# Power_Circuit.net
KiCad netlist of a schematic drawn in Altium Designer
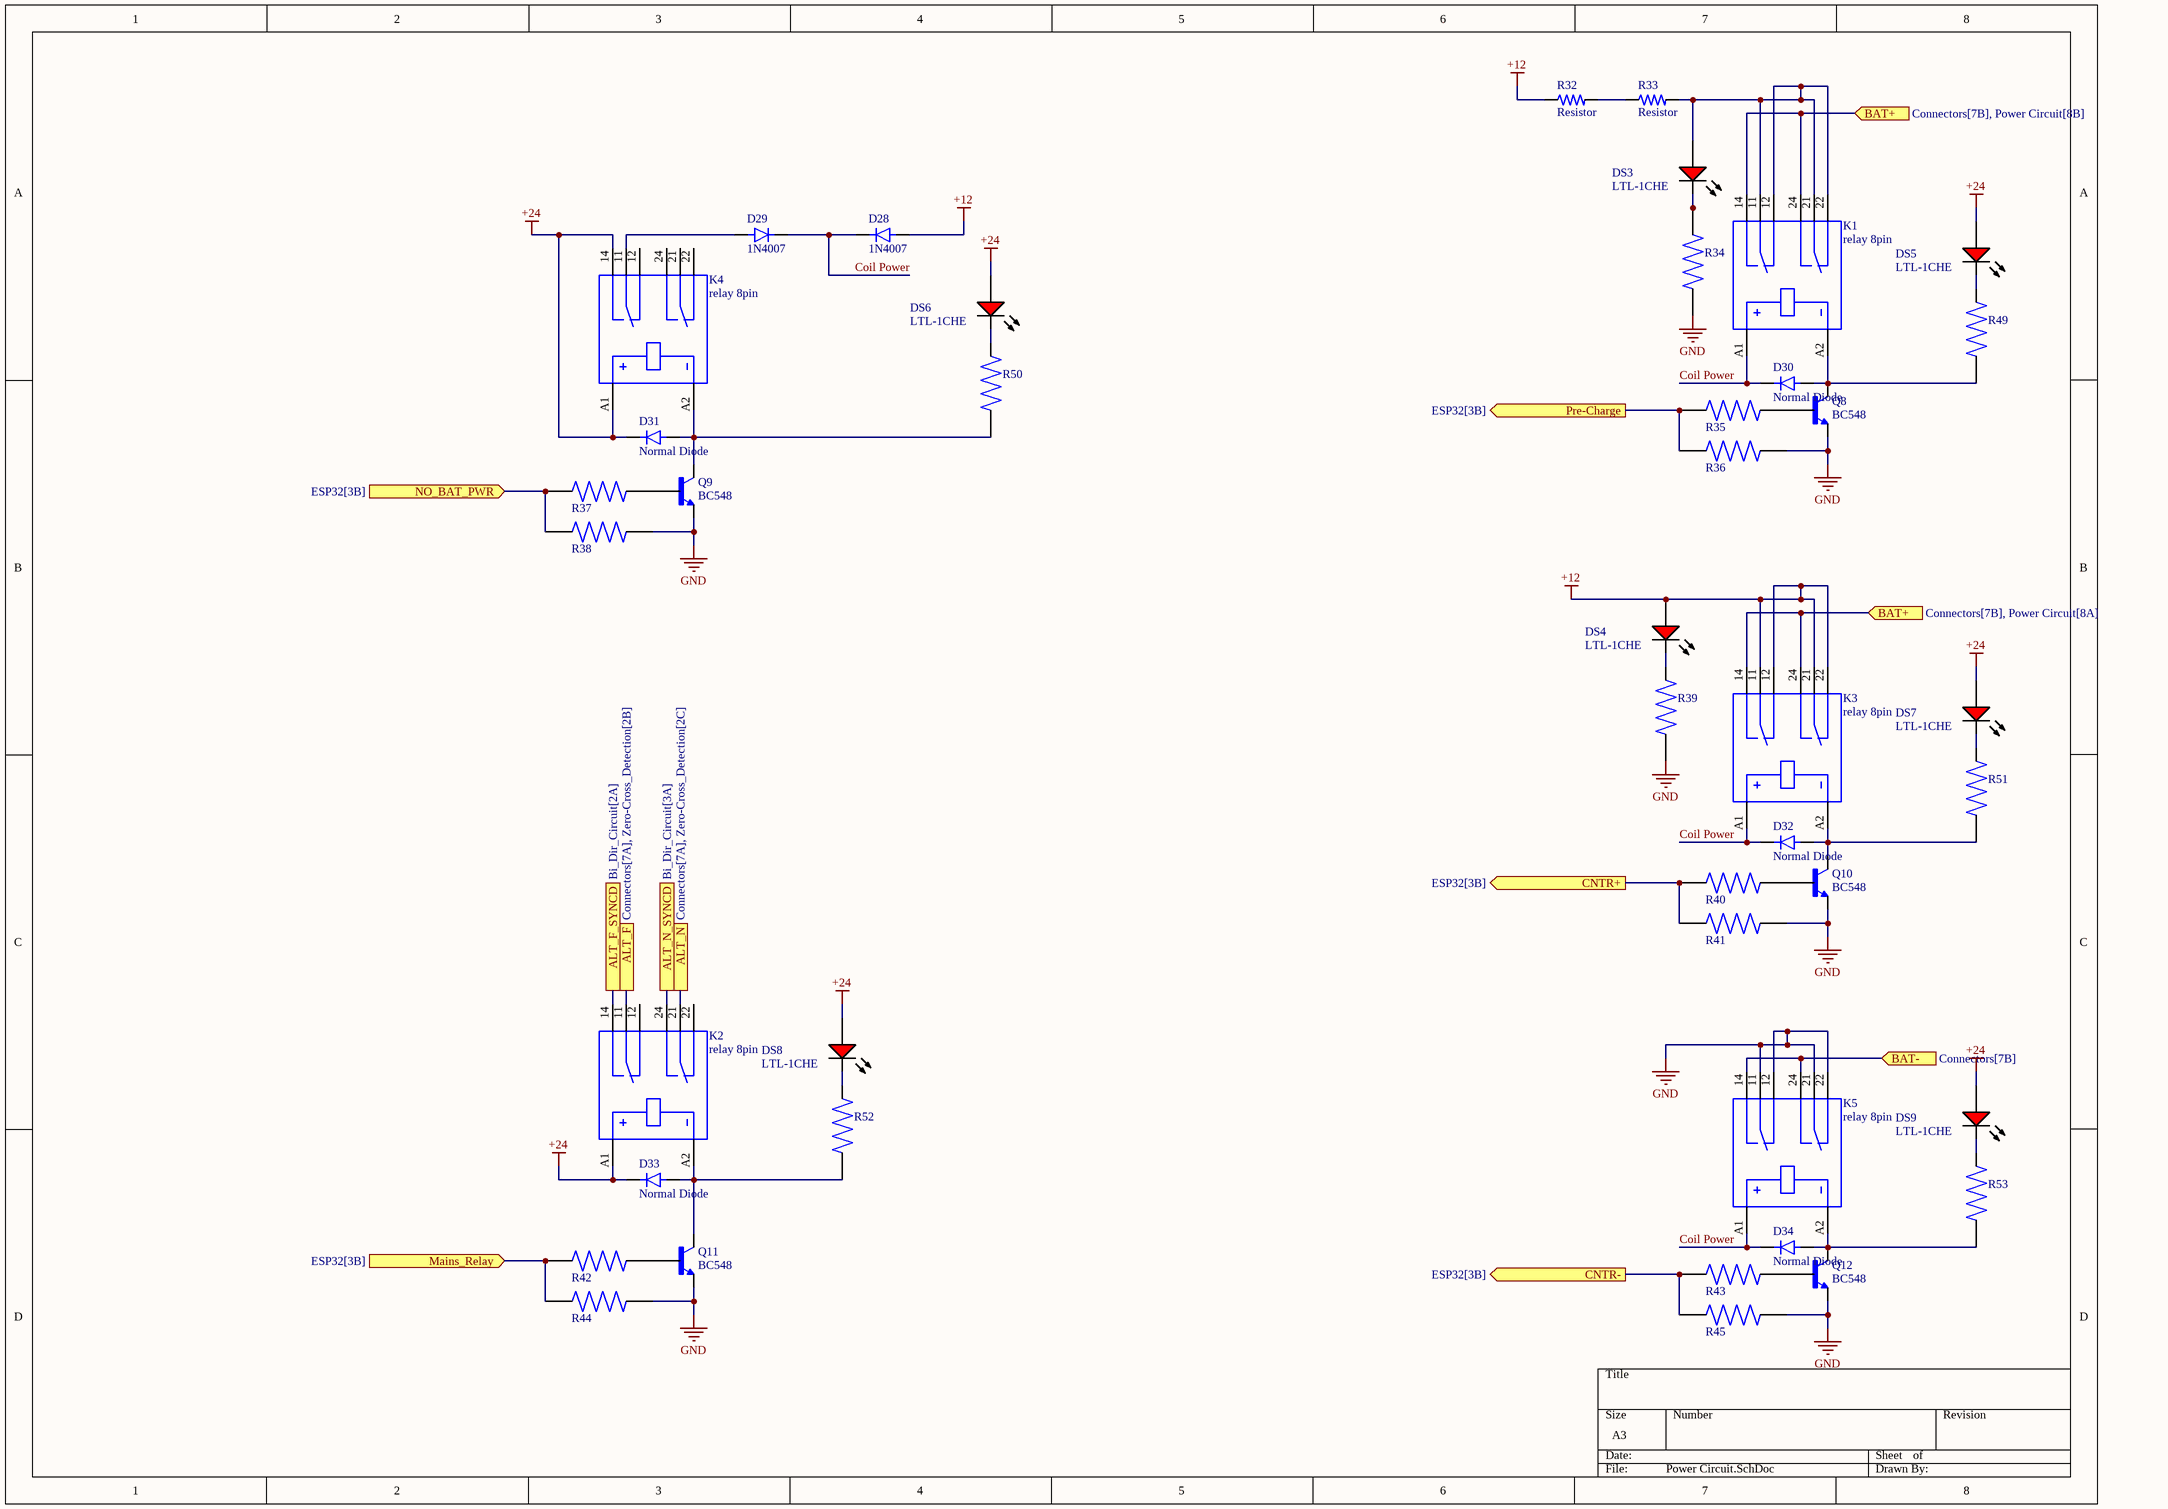
[diagram p0: Power Circuit.SchDoc]

(export (version "E")
  (design (tool "Eeschema 10.0.6"))
  (components
    (comp (ref "D28")
      (value "1N4007")
      (footprint "Common Trhough Hole")
      (fields (field (name "MF") "NTE Electronics, Inc."))
      (libsource (lib "Diodes Through Hole") (part "Normal Diode"))
    )
    (comp (ref "D29")
      (value "1N4007")
      (footprint "Common Trhough Hole")
      (fields (field (name "MF") "NTE Electronics, Inc."))
      (libsource (lib "Diodes Through Hole") (part "Normal Diode"))
    )
    (comp (ref "D30")
      (value "Normal Diode")
      (footprint "Common Trhough Hole")
      (fields (field (name "MF") "NTE Electronics, Inc.") (field (name "MP") "1N4007"))
      (libsource (lib "Diodes Through Hole") (part "Normal Diode"))
    )
    (comp (ref "D31")
      (value "Normal Diode")
      (footprint "Common Trhough Hole")
      (fields (field (name "MF") "NTE Electronics, Inc.") (field (name "MP") "1N4007"))
      (libsource (lib "Diodes Through Hole") (part "Normal Diode"))
    )
    (comp (ref "D32")
      (value "Normal Diode")
      (footprint "Common Trhough Hole")
      (fields (field (name "MF") "NTE Electronics, Inc.") (field (name "MP") "1N4007"))
      (libsource (lib "Diodes Through Hole") (part "Normal Diode"))
    )
    (comp (ref "D33")
      (value "Normal Diode")
      (footprint "Common Trhough Hole")
      (fields (field (name "MF") "NTE Electronics, Inc.") (field (name "MP") "1N4007"))
      (libsource (lib "Diodes Through Hole") (part "Normal Diode"))
    )
    (comp (ref "D34")
      (value "Normal Diode")
      (footprint "Common Trhough Hole")
      (fields (field (name "MF") "NTE Electronics, Inc.") (field (name "MP") "1N4007"))
      (libsource (lib "Diodes Through Hole") (part "Normal Diode"))
    )
    (comp (ref "DS3")
      (value "LTL-1CHE")
      (footprint "LED3mm")
      (description "Radial LED, 12.6 mcd, 20 mA, 2 V, -55 to 100 degC, 2-Pin THD, RoHS, Bulk")
      (fields (field (name "TOLERANCE") "20%"))
      (libsource (lib "MySCH_Library") (part "RED_LED 3mm"))
    )
    (comp (ref "DS4")
      (value "LTL-1CHE")
      (footprint "LED3mm")
      (description "Radial LED, 12.6 mcd, 20 mA, 2 V, -55 to 100 degC, 2-Pin THD, RoHS, Bulk")
      (fields (field (name "TOLERANCE") "20%"))
      (libsource (lib "MySCH_Library") (part "RED_LED 3mm"))
    )
    (comp (ref "DS5")
      (value "LTL-1CHE")
      (footprint "LED3mm")
      (description "Radial LED, 12.6 mcd, 20 mA, 2 V, -55 to 100 degC, 2-Pin THD, RoHS, Bulk")
      (fields (field (name "TOLERANCE") "20%"))
      (libsource (lib "MySCH_Library") (part "RED_LED 3mm"))
    )
    (comp (ref "DS6")
      (value "LTL-1CHE")
      (footprint "LED3mm")
      (description "Radial LED, 12.6 mcd, 20 mA, 2 V, -55 to 100 degC, 2-Pin THD, RoHS, Bulk")
      (fields (field (name "TOLERANCE") "20%"))
      (libsource (lib "MySCH_Library") (part "RED_LED 3mm"))
    )
    (comp (ref "DS7")
      (value "LTL-1CHE")
      (footprint "LED3mm")
      (description "Radial LED, 12.6 mcd, 20 mA, 2 V, -55 to 100 degC, 2-Pin THD, RoHS, Bulk")
      (fields (field (name "TOLERANCE") "20%"))
      (libsource (lib "MySCH_Library") (part "RED_LED 3mm"))
    )
    (comp (ref "DS8")
      (value "LTL-1CHE")
      (footprint "LED3mm")
      (description "Radial LED, 12.6 mcd, 20 mA, 2 V, -55 to 100 degC, 2-Pin THD, RoHS, Bulk")
      (fields (field (name "TOLERANCE") "20%"))
      (libsource (lib "MySCH_Library") (part "RED_LED 3mm"))
    )
    (comp (ref "DS9")
      (value "LTL-1CHE")
      (footprint "LED3mm")
      (description "Radial LED, 12.6 mcd, 20 mA, 2 V, -55 to 100 degC, 2-Pin THD, RoHS, Bulk")
      (fields (field (name "TOLERANCE") "20%"))
      (libsource (lib "MySCH_Library") (part "RED_LED 3mm"))
    )
    (comp (ref "K1")
      (value "relay 8pin")
      (footprint "Relay socket 8pin")
      (description "General Purpose Relay DPDT _2 Form C_ 24VDC Coil Through Hole")
      (fields (field (name "MF") "TE Connectivity") (field (name "MP") "1-1393243-0"))
      (libsource (lib "MySCH_Library") (part "relay 8pin"))
    )
    (comp (ref "K2")
      (value "relay 8pin")
      (footprint "Relay socket 8pin")
      (description "General Purpose Relay DPDT _2 Form C_ 24VDC Coil Through Hole")
      (fields (field (name "MF") "TE Connectivity") (field (name "MP") "1-1393243-0"))
      (libsource (lib "MySCH_Library") (part "relay 8pin"))
    )
    (comp (ref "K3")
      (value "relay 8pin")
      (footprint "Relay socket 8pin")
      (description "General Purpose Relay DPDT _2 Form C_ 24VDC Coil Through Hole")
      (fields (field (name "MF") "TE Connectivity") (field (name "MP") "1-1393243-0"))
      (libsource (lib "MySCH_Library") (part "relay 8pin"))
    )
    (comp (ref "K4")
      (value "relay 8pin")
      (footprint "Relay socket 8pin")
      (description "General Purpose Relay DPDT _2 Form C_ 24VDC Coil Through Hole")
      (fields (field (name "MF") "TE Connectivity") (field (name "MP") "1-1393243-0"))
      (libsource (lib "MySCH_Library") (part "relay 8pin"))
    )
    (comp (ref "K5")
      (value "relay 8pin")
      (footprint "Relay socket 8pin")
      (description "General Purpose Relay DPDT _2 Form C_ 24VDC Coil Through Hole")
      (fields (field (name "MF") "TE Connectivity") (field (name "MP") "1-1393243-0"))
      (libsource (lib "MySCH_Library") (part "relay 8pin"))
    )
    (comp (ref "Q8")
      (value "BC548")
      (footprint "bc548")
      (description "Bipolar (BJT) Transistor NPN 30V 100mA 300MHz 500mW Through Hole TO-92-3")
      (fields (field (name "MF") "ON Semiconductor"))
      (libsource (lib "MySCH_Library") (part "BC548"))
    )
    (comp (ref "Q9")
      (value "BC548")
      (footprint "bc548")
      (description "Bipolar (BJT) Transistor NPN 30V 100mA 300MHz 500mW Through Hole TO-92-3")
      (fields (field (name "MF") "ON Semiconductor"))
      (libsource (lib "MySCH_Library") (part "BC548"))
    )
    (comp (ref "Q10")
      (value "BC548")
      (footprint "bc548")
      (description "Bipolar (BJT) Transistor NPN 30V 100mA 300MHz 500mW Through Hole TO-92-3")
      (fields (field (name "MF") "ON Semiconductor"))
      (libsource (lib "MySCH_Library") (part "BC548"))
    )
    (comp (ref "Q11")
      (value "BC548")
      (footprint "bc548")
      (description "Bipolar (BJT) Transistor NPN 30V 100mA 300MHz 500mW Through Hole TO-92-3")
      (fields (field (name "MF") "ON Semiconductor"))
      (libsource (lib "MySCH_Library") (part "BC548"))
    )
    (comp (ref "Q12")
      (value "BC548")
      (footprint "bc548")
      (description "Bipolar (BJT) Transistor NPN 30V 100mA 300MHz 500mW Through Hole TO-92-3")
      (fields (field (name "MF") "ON Semiconductor"))
      (libsource (lib "MySCH_Library") (part "BC548"))
    )
    (comp (ref "R32")
      (value "Resistor")
      (footprint "Resistor_Through Hole")
      (fields
        (field (name "MP") "2-2176053-0")
        (field (name "TOLERANCE") "1%")
        (field (name "MF") "TE Connectivity")
      )
      (libsource (lib "Resistors Through Hole") (part "Resistor"))
    )
    (comp (ref "R33")
      (value "Resistor")
      (footprint "Resistor_Through Hole")
      (fields
        (field (name "MP") "2-2176053-0")
        (field (name "TOLERANCE") "1%")
        (field (name "MF") "TE Connectivity")
      )
      (libsource (lib "Resistors Through Hole") (part "Resistor"))
    )
    (comp (ref "R34")
      (value "Resistor_Through Hole")
      (footprint "Resistor_Through Hole")
      (description "1.02 Ohms Â±1% 0.25W, 1/4W Through Hole Resistor Axial Metal Film")
      (fields (field (name "MP") "MFR-25FTE52-1R") (field (name "MF") "Yageo"))
      (libsource (lib "MySCH_Library") (part "Resistor_Through Hole"))
    )
    (comp (ref "R35")
      (value "Resistor_Through Hole")
      (footprint "Resistor_Through Hole")
      (description "1.02 Ohms Â±1% 0.25W, 1/4W Through Hole Resistor Axial Metal Film")
      (fields (field (name "MP") "MFR-25FTE52-1R") (field (name "MF") "Yageo"))
      (libsource (lib "MySCH_Library") (part "Resistor_Through Hole"))
    )
    (comp (ref "R36")
      (value "Resistor_Through Hole")
      (footprint "Resistor_Through Hole")
      (description "1.02 Ohms Â±1% 0.25W, 1/4W Through Hole Resistor Axial Metal Film")
      (fields (field (name "MP") "MFR-25FTE52-1R") (field (name "MF") "Yageo"))
      (libsource (lib "MySCH_Library") (part "Resistor_Through Hole"))
    )
    (comp (ref "R37")
      (value "Resistor_Through Hole")
      (footprint "Resistor_Through Hole")
      (description "1.02 Ohms Â±1% 0.25W, 1/4W Through Hole Resistor Axial Metal Film")
      (fields (field (name "MP") "MFR-25FTE52-1R") (field (name "MF") "Yageo"))
      (libsource (lib "MySCH_Library") (part "Resistor_Through Hole"))
    )
    (comp (ref "R38")
      (value "Resistor_Through Hole")
      (footprint "Resistor_Through Hole")
      (description "1.02 Ohms Â±1% 0.25W, 1/4W Through Hole Resistor Axial Metal Film")
      (fields (field (name "MP") "MFR-25FTE52-1R") (field (name "MF") "Yageo"))
      (libsource (lib "MySCH_Library") (part "Resistor_Through Hole"))
    )
    (comp (ref "R39")
      (value "Resistor_Through Hole")
      (footprint "Resistor_Through Hole")
      (description "1.02 Ohms Â±1% 0.25W, 1/4W Through Hole Resistor Axial Metal Film")
      (fields (field (name "MP") "MFR-25FTE52-1R") (field (name "MF") "Yageo"))
      (libsource (lib "MySCH_Library") (part "Resistor_Through Hole"))
    )
    (comp (ref "R40")
      (value "Resistor_Through Hole")
      (footprint "Resistor_Through Hole")
      (description "1.02 Ohms Â±1% 0.25W, 1/4W Through Hole Resistor Axial Metal Film")
      (fields (field (name "MP") "MFR-25FTE52-1R") (field (name "MF") "Yageo"))
      (libsource (lib "MySCH_Library") (part "Resistor_Through Hole"))
    )
    (comp (ref "R41")
      (value "Resistor_Through Hole")
      (footprint "Resistor_Through Hole")
      (description "1.02 Ohms Â±1% 0.25W, 1/4W Through Hole Resistor Axial Metal Film")
      (fields (field (name "MP") "MFR-25FTE52-1R") (field (name "MF") "Yageo"))
      (libsource (lib "MySCH_Library") (part "Resistor_Through Hole"))
    )
    (comp (ref "R42")
      (value "Resistor_Through Hole")
      (footprint "Resistor_Through Hole")
      (description "1.02 Ohms Â±1% 0.25W, 1/4W Through Hole Resistor Axial Metal Film")
      (fields (field (name "MP") "MFR-25FTE52-1R") (field (name "MF") "Yageo"))
      (libsource (lib "MySCH_Library") (part "Resistor_Through Hole"))
    )
    (comp (ref "R43")
      (value "Resistor_Through Hole")
      (footprint "Resistor_Through Hole")
      (description "1.02 Ohms Â±1% 0.25W, 1/4W Through Hole Resistor Axial Metal Film")
      (fields (field (name "MP") "MFR-25FTE52-1R") (field (name "MF") "Yageo"))
      (libsource (lib "MySCH_Library") (part "Resistor_Through Hole"))
    )
    (comp (ref "R44")
      (value "Resistor_Through Hole")
      (footprint "Resistor_Through Hole")
      (description "1.02 Ohms Â±1% 0.25W, 1/4W Through Hole Resistor Axial Metal Film")
      (fields (field (name "MP") "MFR-25FTE52-1R") (field (name "MF") "Yageo"))
      (libsource (lib "MySCH_Library") (part "Resistor_Through Hole"))
    )
    (comp (ref "R45")
      (value "Resistor_Through Hole")
      (footprint "Resistor_Through Hole")
      (description "1.02 Ohms Â±1% 0.25W, 1/4W Through Hole Resistor Axial Metal Film")
      (fields (field (name "MP") "MFR-25FTE52-1R") (field (name "MF") "Yageo"))
      (libsource (lib "MySCH_Library") (part "Resistor_Through Hole"))
    )
    (comp (ref "R49")
      (value "Resistor_Through Hole")
      (footprint "Resistor_Through Hole")
      (description "1.02 Ohms Â±1% 0.25W, 1/4W Through Hole Resistor Axial Metal Film")
      (fields (field (name "MP") "MFR-25FTE52-1R") (field (name "MF") "Yageo"))
      (libsource (lib "MySCH_Library") (part "Resistor_Through Hole"))
    )
    (comp (ref "R50")
      (value "Resistor_Through Hole")
      (footprint "Resistor_Through Hole")
      (description "1.02 Ohms Â±1% 0.25W, 1/4W Through Hole Resistor Axial Metal Film")
      (fields (field (name "MP") "MFR-25FTE52-1R") (field (name "MF") "Yageo"))
      (libsource (lib "MySCH_Library") (part "Resistor_Through Hole"))
    )
    (comp (ref "R51")
      (value "Resistor_Through Hole")
      (footprint "Resistor_Through Hole")
      (description "1.02 Ohms Â±1% 0.25W, 1/4W Through Hole Resistor Axial Metal Film")
      (fields (field (name "MP") "MFR-25FTE52-1R") (field (name "MF") "Yageo"))
      (libsource (lib "MySCH_Library") (part "Resistor_Through Hole"))
    )
    (comp (ref "R52")
      (value "Resistor_Through Hole")
      (footprint "Resistor_Through Hole")
      (description "1.02 Ohms Â±1% 0.25W, 1/4W Through Hole Resistor Axial Metal Film")
      (fields (field (name "MP") "MFR-25FTE52-1R") (field (name "MF") "Yageo"))
      (libsource (lib "MySCH_Library") (part "Resistor_Through Hole"))
    )
    (comp (ref "R53")
      (value "Resistor_Through Hole")
      (footprint "Resistor_Through Hole")
      (description "1.02 Ohms Â±1% 0.25W, 1/4W Through Hole Resistor Axial Metal Film")
      (fields (field (name "MP") "MFR-25FTE52-1R") (field (name "MF") "Yageo"))
      (libsource (lib "MySCH_Library") (part "Resistor_Through Hole"))
    )
  )
  (nets
    (net (code "1") (name "+12") (class "Default")
      (node (ref "D28") (pin "2") (pinfunction "A_2") (pintype "passive"))
      (node (ref "DS4") (pin "1") (pinfunction "A_1") (pintype "passive"))
      (node (ref "K3") (pin "11") (pinfunction "6_11") (pintype "passive"))
      (node (ref "K3") (pin "12") (pinfunction "7_12") (pintype "passive"))
      (node (ref "K3") (pin "21") (pinfunction "3_21") (pintype "passive"))
      (node (ref "K3") (pin "22") (pinfunction "2_22") (pintype "passive"))
      (node (ref "R32") (pin "1") (pinfunction "1_1") (pintype "passive"))
    )
    (net (code "2") (name "+24") (class "Default")
      (node (ref "D31") (pin "1") (pinfunction "K_1") (pintype "passive"))
      (node (ref "D33") (pin "1") (pinfunction "K_1") (pintype "passive"))
      (node (ref "DS5") (pin "1") (pinfunction "A_1") (pintype "passive"))
      (node (ref "DS6") (pin "1") (pinfunction "A_1") (pintype "passive"))
      (node (ref "DS7") (pin "1") (pinfunction "A_1") (pintype "passive"))
      (node (ref "DS8") (pin "1") (pinfunction "A_1") (pintype "passive"))
      (node (ref "DS9") (pin "1") (pinfunction "A_1") (pintype "passive"))
      (node (ref "K2") (pin "A1") (pinfunction "1_A1") (pintype "passive"))
      (node (ref "K4") (pin "14") (pinfunction "5_14") (pintype "passive"))
      (node (ref "K4") (pin "A1") (pinfunction "1_A1") (pintype "passive"))
    )
    (net (code "3") (name "/ALT_F") (class "Default")
      (node (ref "K2") (pin "11") (pinfunction "6_11") (pintype "passive"))
    )
    (net (code "4") (name "/ALT_F_SYNCD") (class "Default")
      (node (ref "K2") (pin "14") (pinfunction "5_14") (pintype "passive"))
    )
    (net (code "5") (name "/ALT_N") (class "Default")
      (node (ref "K2") (pin "21") (pinfunction "3_21") (pintype "passive"))
    )
    (net (code "6") (name "/ALT_N_SYNCD") (class "Default")
      (node (ref "K2") (pin "24") (pinfunction "4_24") (pintype "passive"))
    )
    (net (code "7") (name "/BAT+") (class "Default")
      (node (ref "K1") (pin "14") (pinfunction "5_14") (pintype "passive"))
      (node (ref "K1") (pin "24") (pinfunction "4_24") (pintype "passive"))
      (node (ref "K3") (pin "14") (pinfunction "5_14") (pintype "passive"))
      (node (ref "K3") (pin "24") (pinfunction "4_24") (pintype "passive"))
    )
    (net (code "8") (name "/BAT-") (class "Default")
      (node (ref "K5") (pin "14") (pinfunction "5_14") (pintype "passive"))
      (node (ref "K5") (pin "24") (pinfunction "4_24") (pintype "passive"))
    )
    (net (code "9") (name "/CNTR+") (class "Default")
      (node (ref "R40") (pin "2") (pinfunction "2_2") (pintype "passive"))
      (node (ref "R41") (pin "2") (pinfunction "2_2") (pintype "passive"))
    )
    (net (code "10") (name "/CNTR-") (class "Default")
      (node (ref "R43") (pin "2") (pinfunction "2_2") (pintype "passive"))
      (node (ref "R45") (pin "2") (pinfunction "2_2") (pintype "passive"))
    )
    (net (code "11") (name "/Coil Power") (class "Default")
      (node (ref "D28") (pin "1") (pinfunction "K_1") (pintype "passive"))
      (node (ref "D29") (pin "1") (pinfunction "K_1") (pintype "passive"))
      (node (ref "D30") (pin "1") (pinfunction "K_1") (pintype "passive"))
      (node (ref "D32") (pin "1") (pinfunction "K_1") (pintype "passive"))
      (node (ref "D34") (pin "1") (pinfunction "K_1") (pintype "passive"))
      (node (ref "K1") (pin "A1") (pinfunction "1_A1") (pintype "passive"))
      (node (ref "K3") (pin "A1") (pinfunction "1_A1") (pintype "passive"))
      (node (ref "K5") (pin "A1") (pinfunction "1_A1") (pintype "passive"))
    )
    (net (code "12") (name "/Mains_Relay") (class "Default")
      (node (ref "R42") (pin "2") (pinfunction "2_2") (pintype "passive"))
      (node (ref "R44") (pin "2") (pinfunction "2_2") (pintype "passive"))
    )
    (net (code "13") (name "/NO_BAT_PWR") (class "Default")
      (node (ref "R37") (pin "2") (pinfunction "2_2") (pintype "passive"))
      (node (ref "R38") (pin "2") (pinfunction "2_2") (pintype "passive"))
    )
    (net (code "14") (name "/Pre-Charge") (class "Default")
      (node (ref "R35") (pin "2") (pinfunction "2_2") (pintype "passive"))
      (node (ref "R36") (pin "2") (pinfunction "2_2") (pintype "passive"))
    )
    (net (code "15") (name "GND") (class "Default")
      (node (ref "K5") (pin "11") (pinfunction "6_11") (pintype "passive"))
      (node (ref "K5") (pin "12") (pinfunction "7_12") (pintype "passive"))
      (node (ref "K5") (pin "21") (pinfunction "3_21") (pintype "passive"))
      (node (ref "K5") (pin "22") (pinfunction "2_22") (pintype "passive"))
      (node (ref "Q10") (pin "3") (pinfunction "E_3") (pintype "passive"))
      (node (ref "Q11") (pin "3") (pinfunction "E_3") (pintype "passive"))
      (node (ref "Q12") (pin "3") (pinfunction "E_3") (pintype "passive"))
      (node (ref "Q8") (pin "3") (pinfunction "E_3") (pintype "passive"))
      (node (ref "Q9") (pin "3") (pinfunction "E_3") (pintype "passive"))
      (node (ref "R34") (pin "2") (pinfunction "2_2") (pintype "passive"))
      (node (ref "R36") (pin "1") (pinfunction "1_1") (pintype "passive"))
      (node (ref "R38") (pin "1") (pinfunction "1_1") (pintype "passive"))
      (node (ref "R39") (pin "2") (pinfunction "2_2") (pintype "passive"))
      (node (ref "R41") (pin "1") (pinfunction "1_1") (pintype "passive"))
      (node (ref "R44") (pin "1") (pinfunction "1_1") (pintype "passive"))
      (node (ref "R45") (pin "1") (pinfunction "1_1") (pintype "passive"))
    )
    (net (code "16") (name "Net-(D29-A)") (class "Default")
      (node (ref "D29") (pin "2") (pinfunction "A_2") (pintype "passive"))
      (node (ref "K4") (pin "11") (pinfunction "6_11") (pintype "passive"))
    )
    (net (code "17") (name "Net-(D30-A)") (class "Default")
      (node (ref "D30") (pin "2") (pinfunction "A_2") (pintype "passive"))
      (node (ref "K1") (pin "A2") (pinfunction "8_A2") (pintype "passive"))
      (node (ref "Q8") (pin "1") (pinfunction "C_1") (pintype "passive"))
      (node (ref "R49") (pin "2") (pinfunction "2_2") (pintype "passive"))
    )
    (net (code "18") (name "Net-(D31-A)") (class "Default")
      (node (ref "D31") (pin "2") (pinfunction "A_2") (pintype "passive"))
      (node (ref "K4") (pin "A2") (pinfunction "8_A2") (pintype "passive"))
      (node (ref "Q9") (pin "1") (pinfunction "C_1") (pintype "passive"))
      (node (ref "R50") (pin "2") (pinfunction "2_2") (pintype "passive"))
    )
    (net (code "19") (name "Net-(D32-A)") (class "Default")
      (node (ref "D32") (pin "2") (pinfunction "A_2") (pintype "passive"))
      (node (ref "K3") (pin "A2") (pinfunction "8_A2") (pintype "passive"))
      (node (ref "Q10") (pin "1") (pinfunction "C_1") (pintype "passive"))
      (node (ref "R51") (pin "2") (pinfunction "2_2") (pintype "passive"))
    )
    (net (code "20") (name "Net-(D33-A)") (class "Default")
      (node (ref "D33") (pin "2") (pinfunction "A_2") (pintype "passive"))
      (node (ref "K2") (pin "A2") (pinfunction "8_A2") (pintype "passive"))
      (node (ref "Q11") (pin "1") (pinfunction "C_1") (pintype "passive"))
      (node (ref "R52") (pin "2") (pinfunction "2_2") (pintype "passive"))
    )
    (net (code "21") (name "Net-(D34-A)") (class "Default")
      (node (ref "D34") (pin "2") (pinfunction "A_2") (pintype "passive"))
      (node (ref "K5") (pin "A2") (pinfunction "8_A2") (pintype "passive"))
      (node (ref "Q12") (pin "1") (pinfunction "C_1") (pintype "passive"))
      (node (ref "R53") (pin "2") (pinfunction "2_2") (pintype "passive"))
    )
    (net (code "22") (name "Net-(DS3-A)") (class "Default")
      (node (ref "DS3") (pin "1") (pinfunction "A_1") (pintype "passive"))
      (node (ref "K1") (pin "11") (pinfunction "6_11") (pintype "passive"))
      (node (ref "K1") (pin "12") (pinfunction "7_12") (pintype "passive"))
      (node (ref "K1") (pin "21") (pinfunction "3_21") (pintype "passive"))
      (node (ref "K1") (pin "22") (pinfunction "2_22") (pintype "passive"))
      (node (ref "R33") (pin "2") (pinfunction "2_2") (pintype "passive"))
    )
    (net (code "23") (name "Net-(DS3-K)") (class "Default")
      (node (ref "DS3") (pin "2") (pinfunction "K_2") (pintype "passive"))
      (node (ref "R34") (pin "1") (pinfunction "1_1") (pintype "passive"))
    )
    (net (code "24") (name "Net-(DS4-K)") (class "Default")
      (node (ref "DS4") (pin "2") (pinfunction "K_2") (pintype "passive"))
      (node (ref "R39") (pin "1") (pinfunction "1_1") (pintype "passive"))
    )
    (net (code "25") (name "Net-(DS5-K)") (class "Default")
      (node (ref "DS5") (pin "2") (pinfunction "K_2") (pintype "passive"))
      (node (ref "R49") (pin "1") (pinfunction "1_1") (pintype "passive"))
    )
    (net (code "26") (name "Net-(DS6-K)") (class "Default")
      (node (ref "DS6") (pin "2") (pinfunction "K_2") (pintype "passive"))
      (node (ref "R50") (pin "1") (pinfunction "1_1") (pintype "passive"))
    )
    (net (code "27") (name "Net-(DS7-K)") (class "Default")
      (node (ref "DS7") (pin "2") (pinfunction "K_2") (pintype "passive"))
      (node (ref "R51") (pin "1") (pinfunction "1_1") (pintype "passive"))
    )
    (net (code "28") (name "Net-(DS8-K)") (class "Default")
      (node (ref "DS8") (pin "2") (pinfunction "K_2") (pintype "passive"))
      (node (ref "R52") (pin "1") (pinfunction "1_1") (pintype "passive"))
    )
    (net (code "29") (name "Net-(DS9-K)") (class "Default")
      (node (ref "DS9") (pin "2") (pinfunction "K_2") (pintype "passive"))
      (node (ref "R53") (pin "1") (pinfunction "1_1") (pintype "passive"))
    )
    (net (code "30") (name "Net-(Q8-B)") (class "Default")
      (node (ref "Q8") (pin "2") (pinfunction "B_2") (pintype "passive"))
      (node (ref "R35") (pin "1") (pinfunction "1_1") (pintype "passive"))
    )
    (net (code "31") (name "Net-(Q9-B)") (class "Default")
      (node (ref "Q9") (pin "2") (pinfunction "B_2") (pintype "passive"))
      (node (ref "R37") (pin "1") (pinfunction "1_1") (pintype "passive"))
    )
    (net (code "32") (name "Net-(Q10-B)") (class "Default")
      (node (ref "Q10") (pin "2") (pinfunction "B_2") (pintype "passive"))
      (node (ref "R40") (pin "1") (pinfunction "1_1") (pintype "passive"))
    )
    (net (code "33") (name "Net-(Q11-B)") (class "Default")
      (node (ref "Q11") (pin "2") (pinfunction "B_2") (pintype "passive"))
      (node (ref "R42") (pin "1") (pinfunction "1_1") (pintype "passive"))
    )
    (net (code "34") (name "Net-(Q12-B)") (class "Default")
      (node (ref "Q12") (pin "2") (pinfunction "B_2") (pintype "passive"))
      (node (ref "R43") (pin "1") (pinfunction "1_1") (pintype "passive"))
    )
    (net (code "35") (name "Net-(R32-Pad2)") (class "Default")
      (node (ref "R32") (pin "2") (pinfunction "2_2") (pintype "passive"))
      (node (ref "R33") (pin "1") (pinfunction "1_1") (pintype "passive"))
    )
    (net (code "36") (name "unconnected-(K2-2-Pad22)") (class "Default")
      (node (ref "K2") (pin "22") (pinfunction "2_22") (pintype "passive"))
    )
    (net (code "37") (name "unconnected-(K2-7-Pad12)") (class "Default")
      (node (ref "K2") (pin "12") (pinfunction "7_12") (pintype "passive"))
    )
    (net (code "38") (name "unconnected-(K4-2-Pad22)") (class "Default")
      (node (ref "K4") (pin "22") (pinfunction "2_22") (pintype "passive"))
    )
    (net (code "39") (name "unconnected-(K4-3-Pad21)") (class "Default")
      (node (ref "K4") (pin "21") (pinfunction "3_21") (pintype "passive"))
    )
    (net (code "40") (name "unconnected-(K4-4-Pad24)") (class "Default")
      (node (ref "K4") (pin "24") (pinfunction "4_24") (pintype "passive"))
    )
    (net (code "41") (name "unconnected-(K4-7-Pad12)") (class "Default")
      (node (ref "K4") (pin "12") (pinfunction "7_12") (pintype "passive"))
    )
  )
)
